# brd.net
KiCad netlist of a schematic drawn in EAGLE
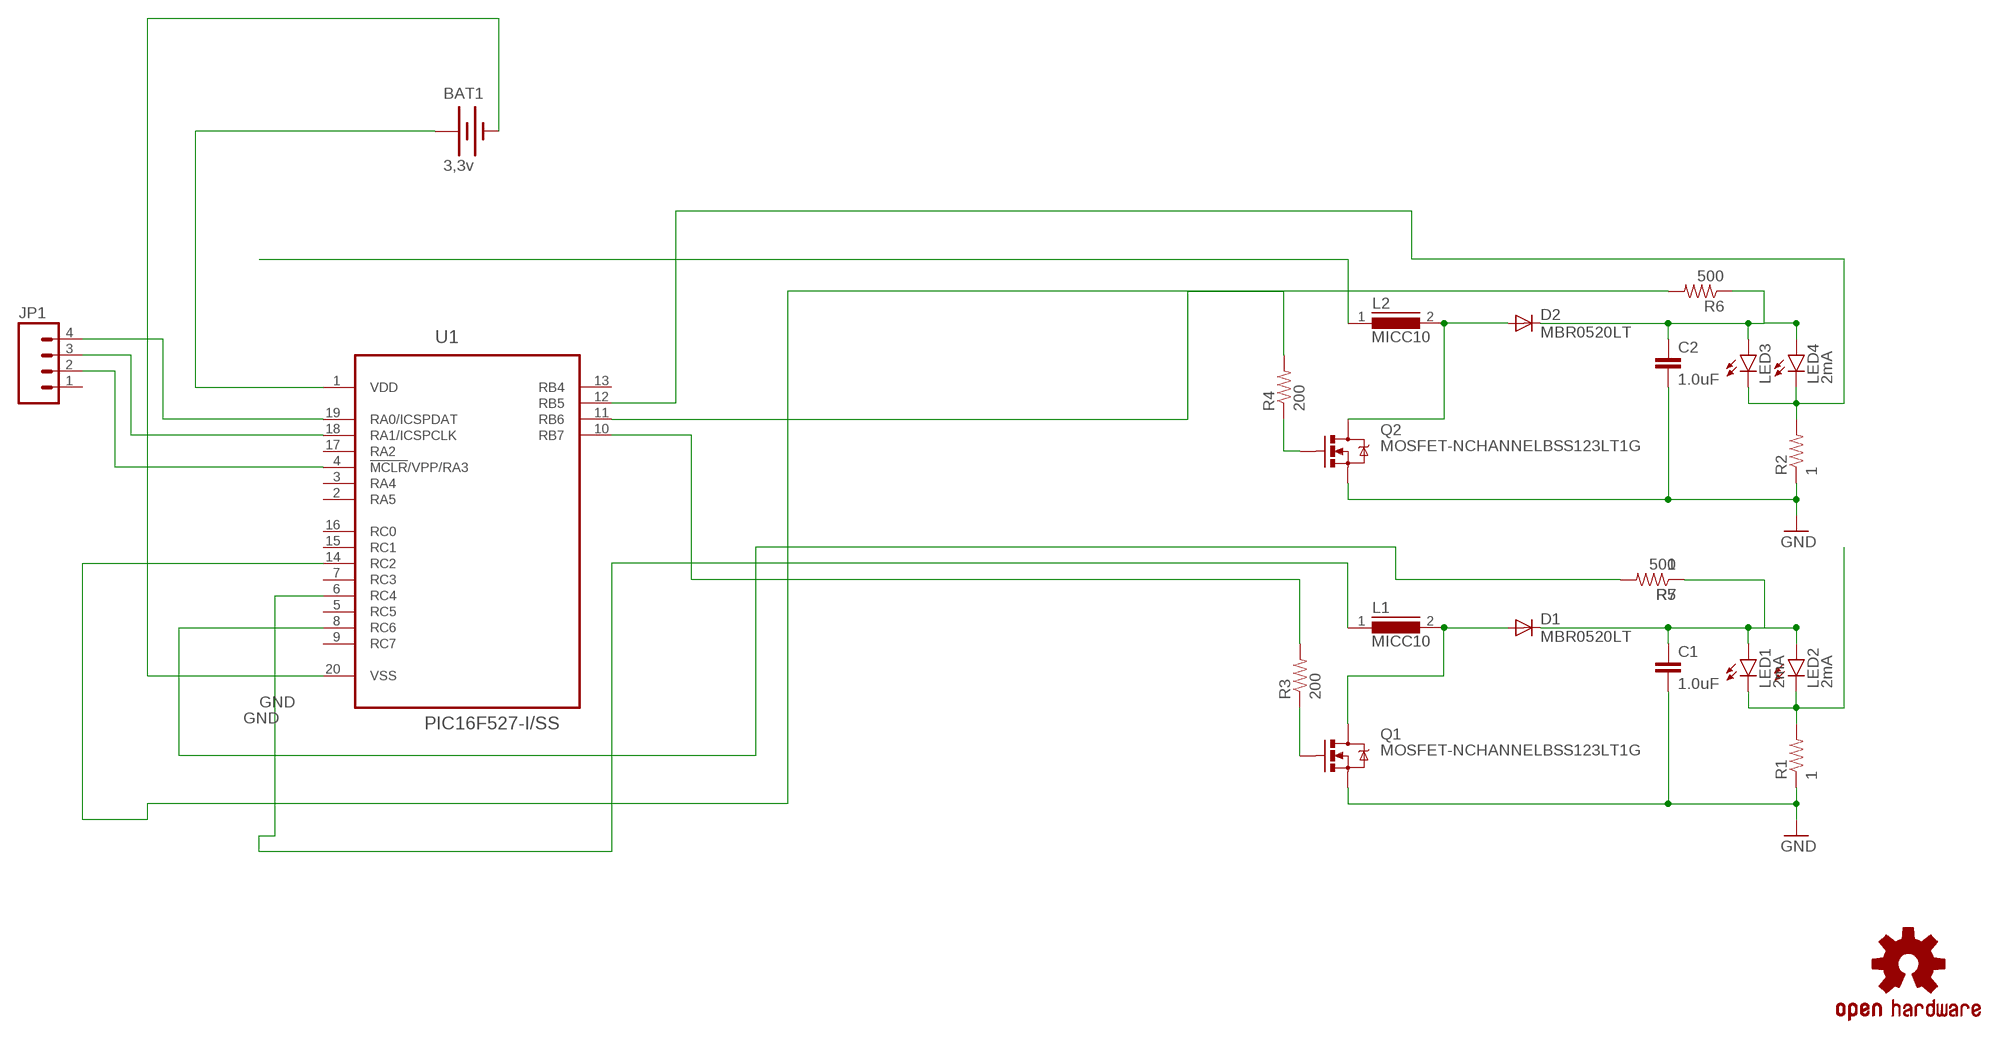
[diagram p0: schematic, sheet 1]

(export (version "E")
  (design (tool "Eeschema 10.0.6"))
  (components
    (comp (ref "BAT1")
      (value "3,3v")
      (footprint "eagle-import:BATTCON_20MM")
      (libsource (lib "eagle-import") (part "BATTERY20SMD"))
    )
    (comp (ref "C1")
      (value "1.0uF")
      (footprint "eagle-import:0805")
      (libsource (lib "eagle-import") (part "1.0UF-25V-+80/-20(0805)"))
    )
    (comp (ref "C2")
      (value "1.0uF")
      (footprint "eagle-import:0805")
      (libsource (lib "eagle-import") (part "1.0UF-25V-+80/-20(0805)"))
    )
    (comp (ref "D1")
      (value "MBR0520LT")
      (footprint "eagle-import:SOD123")
      (libsource (lib "eagle-import") (part "MBR0520LT"))
    )
    (comp (ref "D2")
      (value "MBR0520LT")
      (footprint "eagle-import:SOD123")
      (libsource (lib "eagle-import") (part "MBR0520LT"))
    )
    (comp (ref "JP1")
      (value "M041.27MM")
      (footprint "eagle-import:1X04-1.27MM")
      (libsource (lib "eagle-import") (part "M041.27MM"))
    )
    (comp (ref "L1")
      (value "MICC10")
      (footprint "eagle-import:MICC10")
      (libsource (lib "eagle-import") (part "MICC10"))
    )
    (comp (ref "L2")
      (value "MICC10")
      (footprint "eagle-import:MICC10")
      (libsource (lib "eagle-import") (part "MICC10"))
    )
    (comp (ref "LED1")
      (value "2mA")
      (footprint "eagle-import:LED3MM-NS")
      (libsource (lib "eagle-import") (part "LED-3MM-NO_SILK"))
    )
    (comp (ref "LED2")
      (value "2mA")
      (footprint "eagle-import:LED3MM-NS")
      (libsource (lib "eagle-import") (part "LED-3MM-NO_SILK"))
    )
    (comp (ref "LED3")
      (value "LED-3MM-NO_SILK")
      (footprint "eagle-import:LED3MM-NS")
      (libsource (lib "eagle-import") (part "LED-3MM-NO_SILK"))
    )
    (comp (ref "LED4")
      (value "2mA")
      (footprint "eagle-import:LED3MM-NS")
      (libsource (lib "eagle-import") (part "LED-3MM-NO_SILK"))
    )
    (comp (ref "LOGO1")
      (value "OSHW-LOGOM")
      (footprint "eagle-import:OSHW-LOGO-M")
      (libsource (lib "eagle-import") (part "OSHW-LOGOM"))
    )
    (comp (ref "Q1")
      (value "MOSFET-NCHANNELBSS123LT1G")
      (footprint "eagle-import:SOT23")
      (libsource (lib "eagle-import") (part "MOSFET-NCHANNELBSS123LT1G"))
    )
    (comp (ref "Q2")
      (value "MOSFET-NCHANNELBSS123LT1G")
      (footprint "eagle-import:SOT23")
      (libsource (lib "eagle-import") (part "MOSFET-NCHANNELBSS123LT1G"))
    )
    (comp (ref "R1")
      (value "1")
      (footprint "eagle-import:0805")
      (libsource (lib "eagle-import") (part "RESISTOR0805-RES"))
    )
    (comp (ref "R2")
      (value "1")
      (footprint "eagle-import:0805")
      (libsource (lib "eagle-import") (part "RESISTOR0805-RES"))
    )
    (comp (ref "R3")
      (value "200")
      (footprint "eagle-import:0805")
      (libsource (lib "eagle-import") (part "RESISTOR0805-RES"))
    )
    (comp (ref "R4")
      (value "200")
      (footprint "eagle-import:0805")
      (libsource (lib "eagle-import") (part "RESISTOR0805-RES"))
    )
    (comp (ref "R5")
      (value "1")
      (footprint "eagle-import:0805")
      (libsource (lib "eagle-import") (part "RESISTOR0805-RES"))
    )
    (comp (ref "R6")
      (value "500")
      (footprint "eagle-import:0805")
      (libsource (lib "eagle-import") (part "RESISTOR0805-RES"))
    )
    (comp (ref "R7")
      (value "500")
      (footprint "eagle-import:0805")
      (libsource (lib "eagle-import") (part "RESISTOR0805-RES"))
    )
    (comp (ref "U1")
      (value "PIC16F527-I/SS")
      (footprint "eagle-import:SOP65P780X200-20N")
      (libsource (lib "eagle-import") (part "PIC16F527-I/SS"))
    )
  )
  (nets
    (net (code "1") (name "GND") (class "Default")
      (node (ref "BAT1") (pin "2") (pinfunction "-_2") (pintype "power_in"))
      (node (ref "C1") (pin "2") (pinfunction "2_2") (pintype "passive"))
      (node (ref "C2") (pin "2") (pinfunction "2_2") (pintype "passive"))
      (node (ref "Q1") (pin "2") (pinfunction "S_2") (pintype "passive"))
      (node (ref "Q2") (pin "2") (pinfunction "S_2") (pintype "passive"))
      (node (ref "R1") (pin "1") (pinfunction "1_1") (pintype "passive"))
      (node (ref "R2") (pin "1") (pinfunction "1_1") (pintype "passive"))
      (node (ref "U1") (pin "20") (pinfunction "VSS_20") (pintype "passive"))
    )
    (net (code "2") (name "Net-(BAT1-+)") (class "Default")
      (node (ref "BAT1") (pin "1") (pinfunction "+_1") (pintype "power_in"))
      (node (ref "U1") (pin "1") (pinfunction "VDD_1") (pintype "power_in"))
    )
    (net (code "3") (name "Net-(C1-Pad1)") (class "Default")
      (node (ref "C1") (pin "1") (pinfunction "1_1") (pintype "passive"))
      (node (ref "D1") (pin "C") (pinfunction "C_C") (pintype "passive"))
      (node (ref "LED1") (pin "A") (pinfunction "A_A") (pintype "passive"))
      (node (ref "LED2") (pin "A") (pinfunction "A_A") (pintype "passive"))
      (node (ref "R5") (pin "1") (pinfunction "1_1") (pintype "passive"))
      (node (ref "R7") (pin "1") (pinfunction "1_1") (pintype "passive"))
    )
    (net (code "4") (name "Net-(C2-Pad1)") (class "Default")
      (node (ref "C2") (pin "1") (pinfunction "1_1") (pintype "passive"))
      (node (ref "D2") (pin "C") (pinfunction "C_C") (pintype "passive"))
      (node (ref "LED3") (pin "A") (pinfunction "A_A") (pintype "passive"))
      (node (ref "LED4") (pin "A") (pinfunction "A_A") (pintype "passive"))
      (node (ref "R6") (pin "1") (pinfunction "1_1") (pintype "passive"))
    )
    (net (code "5") (name "Net-(LED1-C)") (class "Default")
      (node (ref "LED1") (pin "K") (pinfunction "C_K") (pintype "passive"))
      (node (ref "LED2") (pin "K") (pinfunction "C_K") (pintype "passive"))
      (node (ref "R1") (pin "2") (pinfunction "2_2") (pintype "passive"))
    )
    (net (code "6") (name "Net-(LED3-C)") (class "Default")
      (node (ref "LED3") (pin "K") (pinfunction "C_K") (pintype "passive"))
      (node (ref "LED4") (pin "K") (pinfunction "C_K") (pintype "passive"))
      (node (ref "R2") (pin "2") (pinfunction "2_2") (pintype "passive"))
      (node (ref "U1") (pin "12") (pinfunction "RB5_12") (pintype "bidirectional"))
    )
    (net (code "7") (name "Net-(Q1-D)") (class "Default")
      (node (ref "D1") (pin "A") (pinfunction "A_A") (pintype "passive"))
      (node (ref "L1") (pin "2") (pinfunction "2_2") (pintype "passive"))
      (node (ref "Q1") (pin "3") (pinfunction "D_3") (pintype "passive"))
    )
    (net (code "8") (name "Net-(Q1-G)") (class "Default")
      (node (ref "Q1") (pin "1") (pinfunction "G_1") (pintype "passive"))
      (node (ref "R3") (pin "1") (pinfunction "1_1") (pintype "passive"))
    )
    (net (code "9") (name "Net-(Q2-D)") (class "Default")
      (node (ref "D2") (pin "A") (pinfunction "A_A") (pintype "passive"))
      (node (ref "L2") (pin "2") (pinfunction "2_2") (pintype "passive"))
      (node (ref "Q2") (pin "3") (pinfunction "D_3") (pintype "passive"))
    )
    (net (code "10") (name "Net-(Q2-G)") (class "Default")
      (node (ref "Q2") (pin "1") (pinfunction "G_1") (pintype "passive"))
      (node (ref "R4") (pin "1") (pinfunction "1_1") (pintype "passive"))
    )
    (net (code "11") (name "Net-(U1-RA0{slash}ICSPDAT)") (class "Default")
      (node (ref "JP1") (pin "4") (pinfunction "4_4") (pintype "passive"))
      (node (ref "U1") (pin "19") (pinfunction "RA0/ICSPDAT_19") (pintype "bidirectional"))
    )
    (net (code "12") (name "Net-(U1-RA1{slash}ICSPCLK)") (class "Default")
      (node (ref "JP1") (pin "3") (pinfunction "3_3") (pintype "passive"))
      (node (ref "U1") (pin "18") (pinfunction "RA1/ICSPCLK_18") (pintype "bidirectional"))
    )
    (net (code "13") (name "Net-(U1-RB6)") (class "Default")
      (node (ref "R4") (pin "2") (pinfunction "2_2") (pintype "passive"))
      (node (ref "U1") (pin "11") (pinfunction "RB6_11") (pintype "bidirectional"))
    )
    (net (code "14") (name "Net-(U1-RB7)") (class "Default")
      (node (ref "R3") (pin "2") (pinfunction "2_2") (pintype "passive"))
      (node (ref "U1") (pin "10") (pinfunction "RB7_10") (pintype "bidirectional"))
    )
    (net (code "15") (name "Net-(U1-RC2)") (class "Default")
      (node (ref "R6") (pin "2") (pinfunction "2_2") (pintype "passive"))
      (node (ref "U1") (pin "14") (pinfunction "RC2_14") (pintype "bidirectional"))
    )
    (net (code "16") (name "Net-(U1-RC4)") (class "Default")
      (node (ref "L1") (pin "1") (pinfunction "1_1") (pintype "passive"))
      (node (ref "U1") (pin "6") (pinfunction "RC4_6") (pintype "bidirectional"))
    )
    (net (code "17") (name "Net-(U1-RC6)") (class "Default")
      (node (ref "R5") (pin "2") (pinfunction "2_2") (pintype "passive"))
      (node (ref "R7") (pin "2") (pinfunction "2_2") (pintype "passive"))
      (node (ref "U1") (pin "8") (pinfunction "RC6_8") (pintype "bidirectional"))
    )
    (net (code "18") (name "Net-(U1-~{MCLR}{slash}VPP{slash}RA3)") (class "Default")
      (node (ref "JP1") (pin "2") (pinfunction "2_2") (pintype "passive"))
      (node (ref "U1") (pin "4") (pinfunction "~{MCLR}/VPP/RA3_4") (pintype "bidirectional"))
    )
    (net (code "19") (name "unconnected-(JP1-Pad1)") (class "Default")
      (node (ref "JP1") (pin "1") (pinfunction "1_1") (pintype "passive"))
    )
    (net (code "20") (name "unconnected-(L2-Pad1)") (class "Default")
      (node (ref "L2") (pin "1") (pinfunction "1_1") (pintype "passive"))
    )
    (net (code "21") (name "unconnected-(U1-RA2-Pad17)") (class "Default")
      (node (ref "U1") (pin "17") (pinfunction "RA2_17") (pintype "bidirectional"))
    )
    (net (code "22") (name "unconnected-(U1-RA4-Pad3)") (class "Default")
      (node (ref "U1") (pin "3") (pinfunction "RA4_3") (pintype "bidirectional"))
    )
    (net (code "23") (name "unconnected-(U1-RA5-Pad2)") (class "Default")
      (node (ref "U1") (pin "2") (pinfunction "RA5_2") (pintype "bidirectional"))
    )
    (net (code "24") (name "unconnected-(U1-RB4-Pad13)") (class "Default")
      (node (ref "U1") (pin "13") (pinfunction "RB4_13") (pintype "bidirectional"))
    )
    (net (code "25") (name "unconnected-(U1-RC0-Pad16)") (class "Default")
      (node (ref "U1") (pin "16") (pinfunction "RC0_16") (pintype "bidirectional"))
    )
    (net (code "26") (name "unconnected-(U1-RC1-Pad15)") (class "Default")
      (node (ref "U1") (pin "15") (pinfunction "RC1_15") (pintype "bidirectional"))
    )
    (net (code "27") (name "unconnected-(U1-RC3-Pad7)") (class "Default")
      (node (ref "U1") (pin "7") (pinfunction "RC3_7") (pintype "bidirectional"))
    )
    (net (code "28") (name "unconnected-(U1-RC5-Pad5)") (class "Default")
      (node (ref "U1") (pin "5") (pinfunction "RC5_5") (pintype "bidirectional"))
    )
    (net (code "29") (name "unconnected-(U1-RC7-Pad9)") (class "Default")
      (node (ref "U1") (pin "9") (pinfunction "RC7_9") (pintype "bidirectional"))
    )
  )
)
